# Recovery.net
KiCad netlist of a schematic drawn in Altium Designer
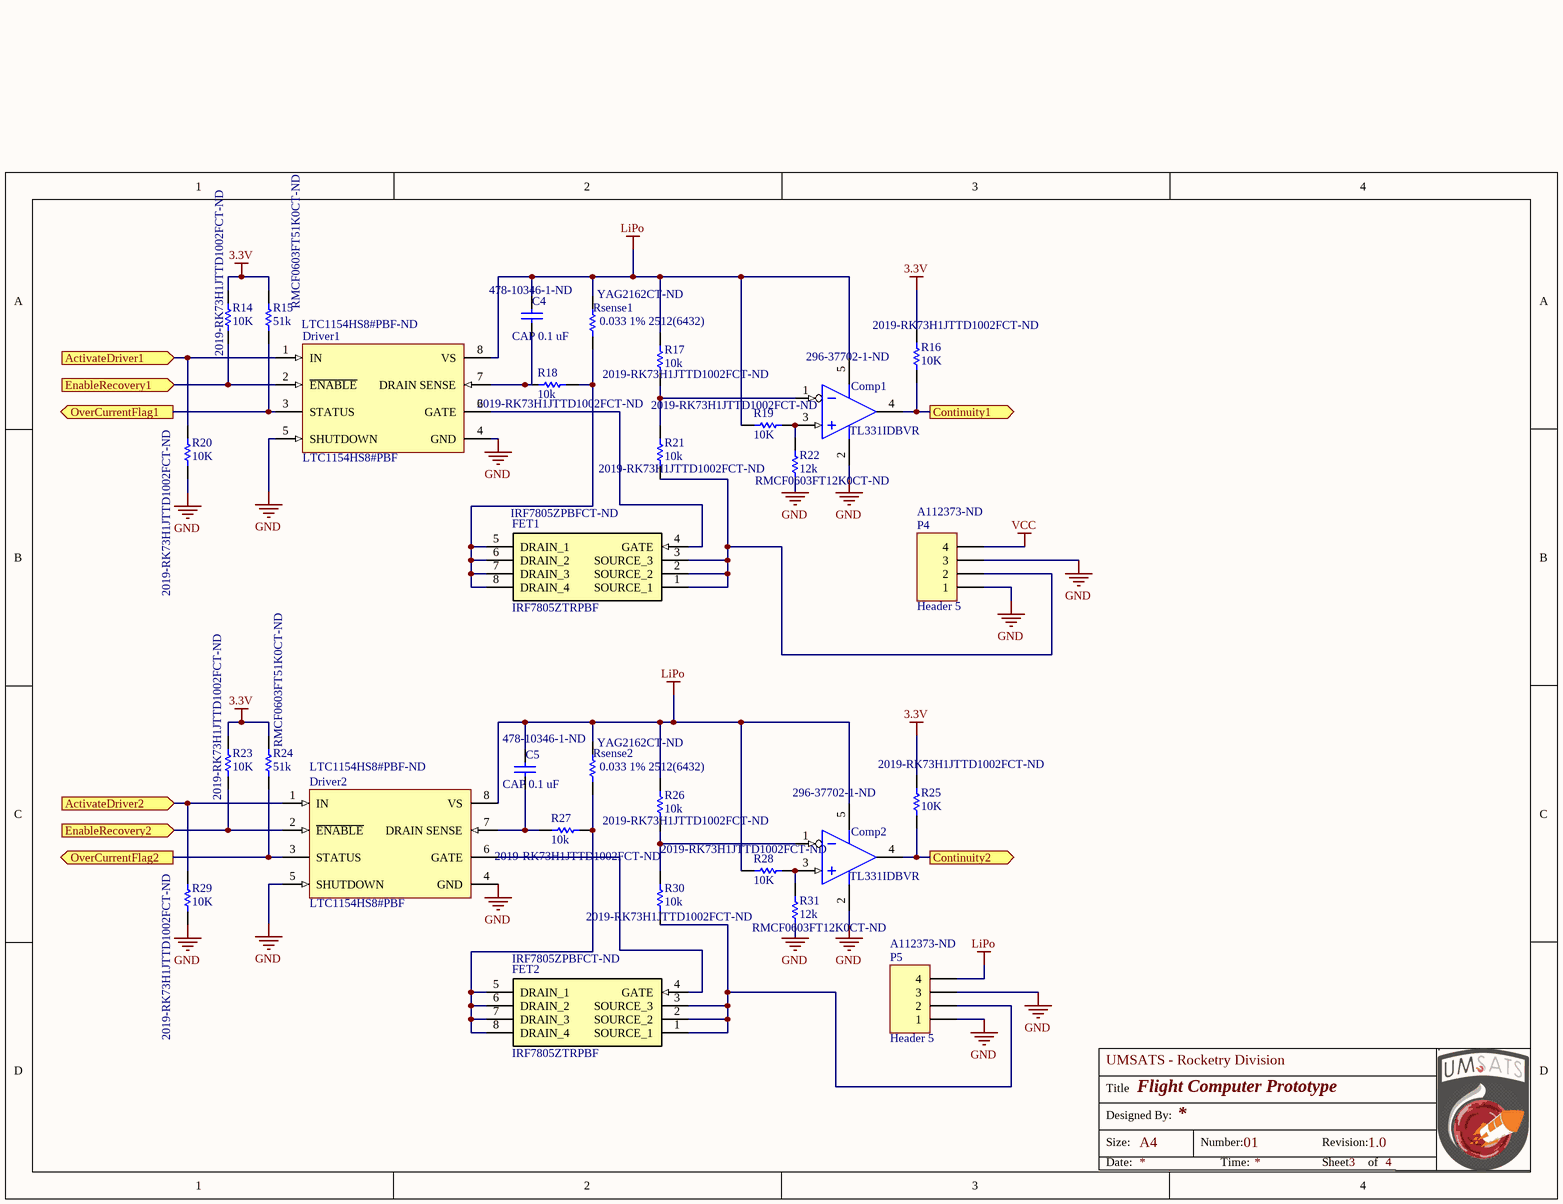
[diagram p0: Recovery.SchDoc]

(export (version "E")
  (design (tool "Eeschema 10.0.6"))
  (components
    (comp (ref "C4")
      (value "CAP 0.1 uF")
      (footprint "06035C104KAT4A")
      (description "Capacitor")
      (fields
        (field (name "SUPPLIER PART NUMBER 1") "478-10346-1-ND")
        (field (name "PUBLISHER") "Altium Limited")
      )
      (libsource (lib "Miscellaneous Devices") (part "Cap"))
    )
    (comp (ref "C5")
      (value "CAP 0.1 uF")
      (footprint "06035C104KAT4A")
      (description "Capacitor")
      (fields
        (field (name "SUPPLIER PART NUMBER 1") "478-10346-1-ND")
        (field (name "PUBLISHER") "Altium Limited")
      )
      (libsource (lib "Miscellaneous Devices") (part "Cap"))
    )
    (comp (ref "Comp1")
      (value "TL331IDBVR")
      (footprint "DBV0005A_M")
      (fields
        (field (name "MANUFACTURER") "TexasInstruments")
        (field (name "SUPPLIER PART NUMBER 1") "296-37702-1-ND")
      )
      (libsource (lib "Altium Content Vault") (part "TI-TL331-EP-DBV5"))
    )
    (comp (ref "Comp2")
      (value "TL331IDBVR")
      (footprint "DBV0005A_M")
      (fields
        (field (name "MANUFACTURER") "TexasInstruments")
        (field (name "SUPPLIER PART NUMBER 1") "296-37702-1-ND")
      )
      (libsource (lib "Altium Content Vault") (part "TI-TL331-EP-DBV5"))
    )
    (comp (ref "Driver1")
      (value "LTC1154HS8#PBF")
      (footprint "LT-S8-8_N")
      (description "High-Side Micropower MOSFET Driver, 22 V Vin MAX, 8-pin SOIC (S8-8), -40 to 150 degC, Pb-Free")
      (fields
        (field (name "MANUFACTURER") "Linear Technology")
        (field (name "SUPPLIER PART NUMBER 1") "LTC1154HS8#PBF-ND")
      )
      (libsource (lib "Altium Content Vault") (part "LT-LTC1154-X8-8"))
    )
    (comp (ref "Driver2")
      (value "LTC1154HS8#PBF")
      (footprint "LT-S8-8_N")
      (description "High-Side Micropower MOSFET Driver, 22 V Vin MAX, 8-pin SOIC (S8-8), -40 to 150 degC, Pb-Free")
      (fields
        (field (name "MANUFACTURER") "Linear Technology")
        (field (name "SUPPLIER PART NUMBER 1") "LTC1154HS8#PBF-ND")
      )
      (libsource (lib "Altium Content Vault") (part "LT-LTC1154-X8-8"))
    )
    (comp (ref "FET1")
      (value "IRF7805ZTRPBF")
      (footprint "SamacSys:SOIC127P600X165-8N")
      (description "MOSFET (N-Channel)")
      (fields
        (field (name "MANUFACTURER_PART_NUMBER") "RSS100N03FRATB")
        (field (name "MOUSER PART NUMBER") "755-RSS100N03FRATB")
        (field (name "SUPPLIER PART NUMBER 1") "IRF7805ZPBFCT-ND")
      )
      (libsource (lib "SamacSys") (part "RSS100N03FRATB"))
    )
    (comp (ref "FET2")
      (value "IRF7805ZTRPBF")
      (footprint "SamacSys:SOIC127P600X165-8N")
      (description "MOSFET (N-Channel)")
      (fields
        (field (name "MANUFACTURER_PART_NUMBER") "RSS100N03FRATB")
        (field (name "MOUSER PART NUMBER") "755-RSS100N03FRATB")
        (field (name "SUPPLIER PART NUMBER 1") "IRF7805ZPBFCT-ND")
      )
      (libsource (lib "SamacSys") (part "RSS100N03FRATB"))
    )
    (comp (ref "P4")
      (value "Header 5")
      (footprint "BarrierBlock6.35mm:BarrierBlock")
      (description "Header, 4-Pin")
      (fields
        (field (name "SUPPLIER PART NUMBER 1") "A112373-ND")
        (field (name "PUBLISHER") "Altium Limited")
      )
      (libsource (lib "Miscellaneous Connectors") (part "Header 4"))
    )
    (comp (ref "P5")
      (value "Header 5")
      (footprint "BarrierBlock6.35mm:BarrierBlock")
      (description "Header, 4-Pin")
      (fields
        (field (name "SUPPLIER PART NUMBER 1") "A112373-ND")
        (field (name "PUBLISHER") "Altium Limited")
      )
      (libsource (lib "Miscellaneous Connectors") (part "Header 4"))
    )
    (comp (ref "R14")
      (value "10K")
      (footprint "RK73H1JTTD1002F")
      (description "Resistor")
      (fields
        (field (name "SUPPLIER PART NUMBER 1") "2019-RK73H1JTTD1002FCT-ND")
        (field (name "PUBLISHER") "Altium Limited")
      )
      (libsource (lib "Miscellaneous Devices") (part "Res1"))
    )
    (comp (ref "R15")
      (value "51k")
      (footprint "RK73H1JTTD1002F")
      (description "Resistor")
      (fields
        (field (name "SUPPLIER PART NUMBER 1") "RMCF0603FT51K0CT-ND")
        (field (name "PUBLISHER") "Altium Limited")
      )
      (libsource (lib "Miscellaneous Devices") (part "Res1"))
    )
    (comp (ref "R16")
      (value "10K")
      (footprint "RK73H1JTTD1002F")
      (description "Resistor")
      (fields
        (field (name "SUPPLIER PART NUMBER 1") "2019-RK73H1JTTD1002FCT-ND")
        (field (name "PUBLISHER") "Altium Limited")
      )
      (libsource (lib "Miscellaneous Devices") (part "Res1"))
    )
    (comp (ref "R17")
      (value "10k")
      (footprint "RK73H1JTTD1002F")
      (description "Resistor")
      (fields
        (field (name "SUPPLIER PART NUMBER 1") "2019-RK73H1JTTD1002FCT-ND")
        (field (name "PUBLISHER") "Altium Limited")
      )
      (libsource (lib "Miscellaneous Devices") (part "Res1"))
    )
    (comp (ref "R18")
      (value "10k")
      (footprint "RK73H1JTTD1002F")
      (description "Resistor")
      (fields
        (field (name "SUPPLIER PART NUMBER 1") "2019-RK73H1JTTD1002FCT-ND")
        (field (name "PUBLISHER") "Altium Limited")
      )
      (libsource (lib "Miscellaneous Devices") (part "Res1"))
    )
    (comp (ref "R19")
      (value "10K")
      (footprint "RK73H1JTTD1002F")
      (description "Resistor")
      (fields
        (field (name "SUPPLIER PART NUMBER 1") "2019-RK73H1JTTD1002FCT-ND")
        (field (name "PUBLISHER") "Altium Limited")
      )
      (libsource (lib "Miscellaneous Devices") (part "Res1"))
    )
    (comp (ref "R20")
      (value "10K")
      (footprint "RK73H1JTTD1002F")
      (description "Resistor")
      (fields
        (field (name "SUPPLIER PART NUMBER 1") "2019-RK73H1JTTD1002FCT-ND")
        (field (name "PUBLISHER") "Altium Limited")
      )
      (libsource (lib "Miscellaneous Devices") (part "Res1"))
    )
    (comp (ref "R21")
      (value "10k")
      (footprint "RK73H1JTTD1002F")
      (description "Resistor")
      (fields
        (field (name "SUPPLIER PART NUMBER 1") "2019-RK73H1JTTD1002FCT-ND")
        (field (name "PUBLISHER") "Altium Limited")
      )
      (libsource (lib "Miscellaneous Devices") (part "Res1"))
    )
    (comp (ref "R22")
      (value "12k")
      (footprint "RK73H1JTTD1002F")
      (description "Resistor")
      (fields
        (field (name "SUPPLIER PART NUMBER 1") "RMCF0603FT12K0CT-ND")
        (field (name "PUBLISHER") "Altium Limited")
      )
      (libsource (lib "Miscellaneous Devices") (part "Res1"))
    )
    (comp (ref "R23")
      (value "10K")
      (footprint "RK73H1JTTD1002F")
      (description "Resistor")
      (fields
        (field (name "SUPPLIER PART NUMBER 1") "2019-RK73H1JTTD1002FCT-ND")
        (field (name "PUBLISHER") "Altium Limited")
      )
      (libsource (lib "Miscellaneous Devices") (part "Res1"))
    )
    (comp (ref "R24")
      (value "51k")
      (footprint "RK73H1JTTD1002F")
      (description "Resistor")
      (fields
        (field (name "SUPPLIER PART NUMBER 1") "RMCF0603FT51K0CT-ND")
        (field (name "PUBLISHER") "Altium Limited")
      )
      (libsource (lib "Miscellaneous Devices") (part "Res1"))
    )
    (comp (ref "R25")
      (value "10K")
      (footprint "RK73H1JTTD1002F")
      (description "Resistor")
      (fields
        (field (name "SUPPLIER PART NUMBER 1") "2019-RK73H1JTTD1002FCT-ND")
        (field (name "PUBLISHER") "Altium Limited")
      )
      (libsource (lib "Miscellaneous Devices") (part "Res1"))
    )
    (comp (ref "R26")
      (value "10k")
      (footprint "RK73H1JTTD1002F")
      (description "Resistor")
      (fields
        (field (name "SUPPLIER PART NUMBER 1") "2019-RK73H1JTTD1002FCT-ND")
        (field (name "PUBLISHER") "Altium Limited")
      )
      (libsource (lib "Miscellaneous Devices") (part "Res1"))
    )
    (comp (ref "R27")
      (value "10k")
      (footprint "RK73H1JTTD1002F")
      (description "Resistor")
      (fields
        (field (name "SUPPLIER PART NUMBER 1") "2019-RK73H1JTTD1002FCT-ND")
        (field (name "PUBLISHER") "Altium Limited")
      )
      (libsource (lib "Miscellaneous Devices") (part "Res1"))
    )
    (comp (ref "R28")
      (value "10K")
      (footprint "RK73H1JTTD1002F")
      (description "Resistor")
      (fields
        (field (name "SUPPLIER PART NUMBER 1") "2019-RK73H1JTTD1002FCT-ND")
        (field (name "PUBLISHER") "Altium Limited")
      )
      (libsource (lib "Miscellaneous Devices") (part "Res1"))
    )
    (comp (ref "R29")
      (value "10K")
      (footprint "RK73H1JTTD1002F")
      (description "Resistor")
      (fields
        (field (name "SUPPLIER PART NUMBER 1") "2019-RK73H1JTTD1002FCT-ND")
        (field (name "PUBLISHER") "Altium Limited")
      )
      (libsource (lib "Miscellaneous Devices") (part "Res1"))
    )
    (comp (ref "R30")
      (value "10k")
      (footprint "RK73H1JTTD1002F")
      (description "Resistor")
      (fields
        (field (name "SUPPLIER PART NUMBER 1") "2019-RK73H1JTTD1002FCT-ND")
        (field (name "PUBLISHER") "Altium Limited")
      )
      (libsource (lib "Miscellaneous Devices") (part "Res1"))
    )
    (comp (ref "R31")
      (value "12k")
      (footprint "RK73H1JTTD1002F")
      (description "Resistor")
      (fields
        (field (name "SUPPLIER PART NUMBER 1") "RMCF0603FT12K0CT-ND")
        (field (name "PUBLISHER") "Altium Limited")
      )
      (libsource (lib "Miscellaneous Devices") (part "Res1"))
    )
    (comp (ref "Rsense1")
      (value "0.033 1% 2512(6432)")
      (footprint "RESC2512(6432)_N")
      (description "8M66 1W 1% 2512 (6432 Metric)  SMD")
      (fields
        (field (name "POWER") "1 W")
        (field (name "TOLERANCE") "1 %")
        (field (name "SUPPLIER PART NUMBER 1") "YAG2162CT-ND")
      )
      (libsource (lib "Altium Content Vault") (part "RES"))
    )
    (comp (ref "Rsense2")
      (value "0.033 1% 2512(6432)")
      (footprint "RESC2512(6432)_N")
      (description "8M66 1W 1% 2512 (6432 Metric)  SMD")
      (fields
        (field (name "POWER") "1 W")
        (field (name "TOLERANCE") "1 %")
        (field (name "SUPPLIER PART NUMBER 1") "YAG2162CT-ND")
      )
      (libsource (lib "Altium Content Vault") (part "RES"))
    )
  )
  (nets
    (net (code "1") (name "/ActivateDriver1") (class "Default")
      (node (ref "Driver1") (pin "1") (pinfunction "IN_1") (pintype "input"))
      (node (ref "R20") (pin "2") (pinfunction "2_2") (pintype "passive"))
    )
    (net (code "2") (name "/ActivateDriver2") (class "Default")
      (node (ref "Driver2") (pin "1") (pinfunction "IN_1") (pintype "input"))
      (node (ref "R29") (pin "2") (pinfunction "2_2") (pintype "passive"))
    )
    (net (code "3") (name "/Continuity1") (class "Default")
      (node (ref "Comp1") (pin "4") (pinfunction "OUT_4") (pintype "tri_state"))
      (node (ref "R16") (pin "1") (pinfunction "1_1") (pintype "passive"))
    )
    (net (code "4") (name "/Continuity2") (class "Default")
      (node (ref "Comp2") (pin "4") (pinfunction "OUT_4") (pintype "tri_state"))
      (node (ref "R25") (pin "1") (pinfunction "1_1") (pintype "passive"))
    )
    (net (code "5") (name "/EnableRecovery1") (class "Default")
      (node (ref "Driver1") (pin "2") (pinfunction "~{ENABLE}_2") (pintype "input"))
      (node (ref "R14") (pin "1") (pinfunction "1_1") (pintype "passive"))
    )
    (net (code "6") (name "/EnableRecovery2") (class "Default")
      (node (ref "Driver2") (pin "2") (pinfunction "~{ENABLE}_2") (pintype "input"))
      (node (ref "R23") (pin "1") (pinfunction "1_1") (pintype "passive"))
    )
    (net (code "7") (name "/OverCurrentFlag1") (class "Default")
      (node (ref "Driver1") (pin "3") (pinfunction "STATUS_3") (pintype "open_collector"))
      (node (ref "R15") (pin "1") (pinfunction "1_1") (pintype "passive"))
    )
    (net (code "8") (name "/OverCurrentFlag2") (class "Default")
      (node (ref "Driver2") (pin "3") (pinfunction "STATUS_3") (pintype "open_collector"))
      (node (ref "R24") (pin "1") (pinfunction "1_1") (pintype "passive"))
    )
    (net (code "9") (name "3.3V") (class "Default")
      (node (ref "R14") (pin "2") (pinfunction "2_2") (pintype "passive"))
      (node (ref "R15") (pin "2") (pinfunction "2_2") (pintype "passive"))
      (node (ref "R16") (pin "2") (pinfunction "2_2") (pintype "passive"))
      (node (ref "R23") (pin "2") (pinfunction "2_2") (pintype "passive"))
      (node (ref "R24") (pin "2") (pinfunction "2_2") (pintype "passive"))
      (node (ref "R25") (pin "2") (pinfunction "2_2") (pintype "passive"))
    )
    (net (code "10") (name "GND") (class "Default")
      (node (ref "Comp1") (pin "2") (pinfunction "VCC-/GND_2") (pintype "power_in"))
      (node (ref "Comp2") (pin "2") (pinfunction "VCC-/GND_2") (pintype "power_in"))
      (node (ref "Driver1") (pin "4") (pinfunction "GND_4") (pintype "power_in"))
      (node (ref "Driver1") (pin "5") (pinfunction "SHUTDOWN_5") (pintype "input"))
      (node (ref "Driver2") (pin "4") (pinfunction "GND_4") (pintype "power_in"))
      (node (ref "Driver2") (pin "5") (pinfunction "SHUTDOWN_5") (pintype "input"))
      (node (ref "P4") (pin "1") (pinfunction "1_1") (pintype "passive"))
      (node (ref "P4") (pin "3") (pinfunction "3_3") (pintype "passive"))
      (node (ref "P5") (pin "1") (pinfunction "1_1") (pintype "passive"))
      (node (ref "P5") (pin "3") (pinfunction "3_3") (pintype "passive"))
      (node (ref "R20") (pin "1") (pinfunction "1_1") (pintype "passive"))
      (node (ref "R22") (pin "1") (pinfunction "1_1") (pintype "passive"))
      (node (ref "R29") (pin "1") (pinfunction "1_1") (pintype "passive"))
      (node (ref "R31") (pin "1") (pinfunction "1_1") (pintype "passive"))
    )
    (net (code "11") (name "LiPo") (class "Default")
      (node (ref "C4") (pin "1") (pinfunction "1_1") (pintype "passive"))
      (node (ref "C5") (pin "1") (pinfunction "1_1") (pintype "passive"))
      (node (ref "Comp1") (pin "5") (pinfunction "VCC_5") (pintype "power_in"))
      (node (ref "Comp2") (pin "5") (pinfunction "VCC_5") (pintype "power_in"))
      (node (ref "Driver1") (pin "8") (pinfunction "VS_8") (pintype "power_in"))
      (node (ref "Driver2") (pin "8") (pinfunction "VS_8") (pintype "power_in"))
      (node (ref "P5") (pin "4") (pinfunction "4_4") (pintype "passive"))
      (node (ref "R17") (pin "2") (pinfunction "2_2") (pintype "passive"))
      (node (ref "R19") (pin "2") (pinfunction "2_2") (pintype "passive"))
      (node (ref "R26") (pin "2") (pinfunction "2_2") (pintype "passive"))
      (node (ref "R28") (pin "2") (pinfunction "2_2") (pintype "passive"))
      (node (ref "Rsense1") (pin "2") (pinfunction "2_2") (pintype "passive"))
      (node (ref "Rsense2") (pin "2") (pinfunction "2_2") (pintype "passive"))
    )
    (net (code "12") (name "Net-(Comp1-IN+)") (class "Default")
      (node (ref "Comp1") (pin "3") (pinfunction "IN+_3") (pintype "input"))
      (node (ref "R19") (pin "1") (pinfunction "1_1") (pintype "passive"))
      (node (ref "R22") (pin "2") (pinfunction "2_2") (pintype "passive"))
    )
    (net (code "13") (name "Net-(Comp1-IN-)") (class "Default")
      (node (ref "Comp1") (pin "1") (pinfunction "IN-_1") (pintype "input"))
      (node (ref "R17") (pin "1") (pinfunction "1_1") (pintype "passive"))
      (node (ref "R21") (pin "2") (pinfunction "2_2") (pintype "passive"))
    )
    (net (code "14") (name "Net-(Comp2-IN+)") (class "Default")
      (node (ref "Comp2") (pin "3") (pinfunction "IN+_3") (pintype "input"))
      (node (ref "R28") (pin "1") (pinfunction "1_1") (pintype "passive"))
      (node (ref "R31") (pin "2") (pinfunction "2_2") (pintype "passive"))
    )
    (net (code "15") (name "Net-(Comp2-IN-)") (class "Default")
      (node (ref "Comp2") (pin "1") (pinfunction "IN-_1") (pintype "input"))
      (node (ref "R26") (pin "1") (pinfunction "1_1") (pintype "passive"))
      (node (ref "R30") (pin "2") (pinfunction "2_2") (pintype "passive"))
    )
    (net (code "16") (name "Net-(Driver1-DRAIN_SENSE)") (class "Default")
      (node (ref "C4") (pin "2") (pinfunction "2_2") (pintype "passive"))
      (node (ref "Driver1") (pin "7") (pinfunction "DRAIN_SENSE_7") (pintype "input"))
      (node (ref "R18") (pin "2") (pinfunction "2_2") (pintype "passive"))
    )
    (net (code "17") (name "Net-(Driver1-GATE)") (class "Default")
      (node (ref "Driver1") (pin "6") (pinfunction "GATE_6") (pintype "tri_state"))
      (node (ref "FET1") (pin "4") (pinfunction "GATE_4") (pintype "input"))
    )
    (net (code "18") (name "Net-(Driver2-DRAIN_SENSE)") (class "Default")
      (node (ref "C5") (pin "2") (pinfunction "2_2") (pintype "passive"))
      (node (ref "Driver2") (pin "7") (pinfunction "DRAIN_SENSE_7") (pintype "input"))
      (node (ref "R27") (pin "2") (pinfunction "2_2") (pintype "passive"))
    )
    (net (code "19") (name "Net-(Driver2-GATE)") (class "Default")
      (node (ref "Driver2") (pin "6") (pinfunction "GATE_6") (pintype "tri_state"))
      (node (ref "FET2") (pin "4") (pinfunction "GATE_4") (pintype "input"))
    )
    (net (code "20") (name "Net-(FET1-DRAIN_1)") (class "Default")
      (node (ref "FET1") (pin "5") (pinfunction "DRAIN_1_5") (pintype "power_in"))
      (node (ref "FET1") (pin "6") (pinfunction "DRAIN_2_6") (pintype "power_in"))
      (node (ref "FET1") (pin "7") (pinfunction "DRAIN_3_7") (pintype "power_in"))
      (node (ref "FET1") (pin "8") (pinfunction "DRAIN_4_8") (pintype "power_in"))
      (node (ref "R18") (pin "1") (pinfunction "1_1") (pintype "passive"))
      (node (ref "Rsense1") (pin "1") (pinfunction "1_1") (pintype "passive"))
    )
    (net (code "21") (name "Net-(FET1-SOURCE_1)") (class "Default")
      (node (ref "FET1") (pin "1") (pinfunction "SOURCE_1_1") (pintype "power_in"))
      (node (ref "FET1") (pin "2") (pinfunction "SOURCE_2_2") (pintype "power_in"))
      (node (ref "FET1") (pin "3") (pinfunction "SOURCE_3_3") (pintype "power_in"))
      (node (ref "P4") (pin "2") (pinfunction "2_2") (pintype "passive"))
      (node (ref "R21") (pin "1") (pinfunction "1_1") (pintype "passive"))
    )
    (net (code "22") (name "Net-(FET2-DRAIN_1)") (class "Default")
      (node (ref "FET2") (pin "5") (pinfunction "DRAIN_1_5") (pintype "power_in"))
      (node (ref "FET2") (pin "6") (pinfunction "DRAIN_2_6") (pintype "power_in"))
      (node (ref "FET2") (pin "7") (pinfunction "DRAIN_3_7") (pintype "power_in"))
      (node (ref "FET2") (pin "8") (pinfunction "DRAIN_4_8") (pintype "power_in"))
      (node (ref "R27") (pin "1") (pinfunction "1_1") (pintype "passive"))
      (node (ref "Rsense2") (pin "1") (pinfunction "1_1") (pintype "passive"))
    )
    (net (code "23") (name "Net-(FET2-SOURCE_1)") (class "Default")
      (node (ref "FET2") (pin "1") (pinfunction "SOURCE_1_1") (pintype "power_in"))
      (node (ref "FET2") (pin "2") (pinfunction "SOURCE_2_2") (pintype "power_in"))
      (node (ref "FET2") (pin "3") (pinfunction "SOURCE_3_3") (pintype "power_in"))
      (node (ref "P5") (pin "2") (pinfunction "2_2") (pintype "passive"))
      (node (ref "R30") (pin "1") (pinfunction "1_1") (pintype "passive"))
    )
    (net (code "24") (name "VCC") (class "Default")
      (node (ref "P4") (pin "4") (pinfunction "4_4") (pintype "passive"))
    )
  )
)
